# EMMC.net
KiCad netlist of a schematic drawn in Altium Designer
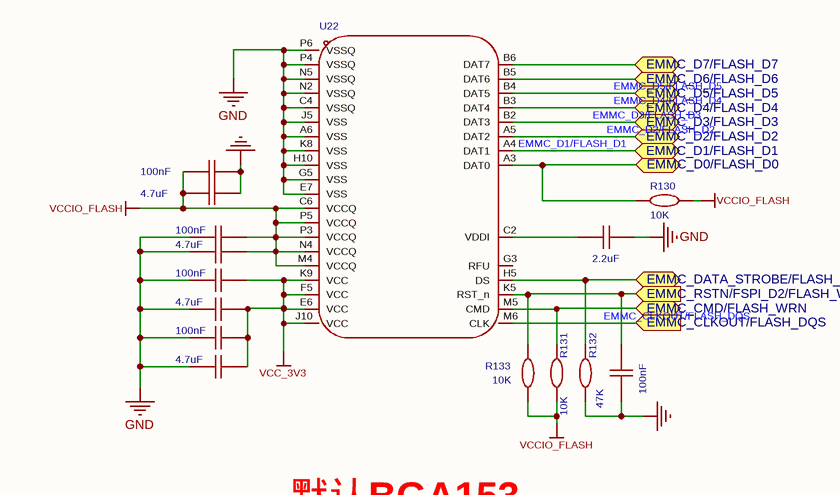
[diagram p0: EMMC.schdoc]

(export (version "E")
  (design (tool "Eeschema 10.0.6"))
  (components
    (comp (ref "C251")
      (value "100nF")
      (footprint "c0402-nsk")
      (description "容值:100nF;精度:±10%;额定电压:50V;材质(温度系数):X7R;")
      (fields (field (name "MANUFACTURER") "YAGEO(国巨)") (field (name "MANUFACTURERPART") "CC0603KRX7R9BB104"))
      (libsource (lib "altium-import") (part "root_0_CC0603KRX7R9BB104_"))
    )
    (comp (ref "C252")
      (value "4.7uF")
      (footprint "c0402-nsk")
      (description "容值:4.7uF;精度:±10%;额定电压:16V;材质(温度系数):X5R;")
      (fields (field (name "MANUFACTURER") "SAMSUNG(三星)") (field (name "MANUFACTURERPART") "CL10A475KO8NNNC"))
      (libsource (lib "altium-import") (part "root_0_CL10A475KO8NNNC_"))
    )
    (comp (ref "C253")
      (value "100nF")
      (footprint "c0402-nsk")
      (description "容值:100nF;精度:±10%;额定电压:50V;材质(温度系数):X7R;")
      (fields (field (name "MANUFACTURER") "YAGEO(国巨)") (field (name "MANUFACTURERPART") "CC0603KRX7R9BB104"))
      (libsource (lib "altium-import") (part "root_0_CC0603KRX7R9BB104_"))
    )
    (comp (ref "C254")
      (value "4.7uF")
      (footprint "c0402-nsk")
      (description "容值:4.7uF;精度:±10%;额定电压:16V;材质(温度系数):X5R;")
      (fields (field (name "MANUFACTURER") "SAMSUNG(三星)") (field (name "MANUFACTURERPART") "CL10A475KO8NNNC"))
      (libsource (lib "altium-import") (part "root_0_CL10A475KO8NNNC_"))
    )
    (comp (ref "C255")
      (value "2.2uF")
      (footprint "c0402-nsk")
      (description "容值:2.2uF;精度:±10%;额定电压:16V;材质(温度系数):X5R;")
      (fields (field (name "MANUFACTURER") "SAMSUNG(三星)") (field (name "MANUFACTURERPART") "CL10A225KO8NNNC"))
      (libsource (lib "altium-import") (part "root_2_CL10A225KO8NNNC_"))
    )
    (comp (ref "C256")
      (value "100nF")
      (footprint "c0402-nsk")
      (description "容值:100nF;精度:±10%;额定电压:50V;材质(温度系数):X7R;")
      (fields (field (name "MANUFACTURER") "YAGEO(国巨)") (field (name "MANUFACTURERPART") "CC0603KRX7R9BB104"))
      (libsource (lib "altium-import") (part "root_0_CC0603KRX7R9BB104_"))
    )
    (comp (ref "C257")
      (value "4.7uF")
      (footprint "c0402-nsk")
      (description "容值:4.7uF;精度:±10%;额定电压:16V;材质(温度系数):X5R;")
      (fields (field (name "MANUFACTURER") "SAMSUNG(三星)") (field (name "MANUFACTURERPART") "CL10A475KO8NNNC"))
      (libsource (lib "altium-import") (part "root_0_CL10A475KO8NNNC_"))
    )
    (comp (ref "C258")
      (value "100nF")
      (footprint "c0402-nsk")
      (description "容值:100nF;精度:±10%;额定电压:50V;材质(温度系数):X7R;")
      (fields (field (name "MANUFACTURER") "YAGEO(国巨)") (field (name "MANUFACTURERPART") "CC0603KRX7R9BB104"))
      (libsource (lib "altium-import") (part "root_0_CC0603KRX7R9BB104_"))
    )
    (comp (ref "C259")
      (value "4.7uF")
      (footprint "c0402-nsk")
      (description "容值:4.7uF;精度:±10%;额定电压:16V;材质(温度系数):X5R;")
      (fields (field (name "MANUFACTURER") "SAMSUNG(三星)") (field (name "MANUFACTURERPART") "CL10A475KO8NNNC"))
      (libsource (lib "altium-import") (part "root_0_CL10A475KO8NNNC_"))
    )
    (comp (ref "C260")
      (value "100nF")
      (footprint "c0402-nsk")
      (description "容值:4.7uF;精度:±10%;额定电压:16V;材质(温度系数):X5R;")
      (fields (field (name "MANUFACTURER") "SAMSUNG(三星)") (field (name "MANUFACTURERPART") "CL10A475KO8NNNC"))
      (libsource (lib "altium-import") (part "root_1_CL10A475KO8NNNC_"))
    )
    (comp (ref "R130")
      (value "10K")
      (footprint "R0402")
      (libsource (lib "altium-import") (part "root_0_Res_0402_"))
    )
    (comp (ref "R131")
      (value "10K")
      (footprint "R0402")
      (libsource (lib "altium-import") (part "root_1_Res_0402_"))
    )
    (comp (ref "R132")
      (value "47K")
      (footprint "R0402")
      (libsource (lib "altium-import") (part "root_1_Res_0402_"))
    )
    (comp (ref "R133")
      (value "10K")
      (footprint "R0402")
      (libsource (lib "altium-import") (part "root_1_Res_0402_"))
    )
    (comp (ref "U22")
      (value "~")
      (footprint "fbga-153_l13.0-w11.5-p0.50_klmag1jetd-b041")
      (fields
        (field (name "MANUFACTURER") "Kingston(金士顿)")
        (field (name "MANUFACTURERPART") "EMMC04G-M627-A01")
      )
      (libsource (lib "altium-import") (part "root_0_EMMC BGA153_"))
    )
  )
  (nets
    (net (code "1") (name "/EMMC_CLKOUT{slash}FLASH_DQS") (class "Default")
      (node (ref "U22") (pin "M6") (pinfunction "CLK_M6") (pintype "passive"))
    )
    (net (code "2") (name "/EMMC_CMD{slash}FLASH_WRN") (class "Default")
      (node (ref "R131") (pin "2") (pinfunction "2_2") (pintype "passive"))
      (node (ref "U22") (pin "M5") (pinfunction "CMD_M5") (pintype "passive"))
    )
    (net (code "3") (name "/EMMC_D0{slash}FLASH_D0") (class "Default")
      (node (ref "R130") (pin "1") (pinfunction "1_1") (pintype "passive"))
      (node (ref "U22") (pin "A3") (pinfunction "DAT0_A3") (pintype "passive"))
    )
    (net (code "4") (name "/EMMC_D1{slash}FLASH_D1") (class "Default")
      (node (ref "U22") (pin "A4") (pinfunction "DAT1_A4") (pintype "passive"))
    )
    (net (code "5") (name "/EMMC_D2{slash}FLASH_D2") (class "Default")
      (node (ref "U22") (pin "A5") (pinfunction "DAT2_A5") (pintype "passive"))
    )
    (net (code "6") (name "/EMMC_D3{slash}FLASH_D3") (class "Default")
      (node (ref "U22") (pin "B2") (pinfunction "DAT3_B2") (pintype "passive"))
    )
    (net (code "7") (name "/EMMC_D4{slash}FLASH_D4") (class "Default")
      (node (ref "U22") (pin "B3") (pinfunction "DAT4_B3") (pintype "passive"))
    )
    (net (code "8") (name "/EMMC_D5{slash}FLASH_D5") (class "Default")
      (node (ref "U22") (pin "B4") (pinfunction "DAT5_B4") (pintype "passive"))
    )
    (net (code "9") (name "/EMMC_D6{slash}FLASH_D6") (class "Default")
      (node (ref "U22") (pin "B5") (pinfunction "DAT6_B5") (pintype "passive"))
    )
    (net (code "10") (name "/EMMC_D7{slash}FLASH_D7") (class "Default")
      (node (ref "U22") (pin "B6") (pinfunction "DAT7_B6") (pintype "passive"))
    )
    (net (code "11") (name "/EMMC_DATA_STROBE{slash}FLASH_CLE") (class "Default")
      (node (ref "R132") (pin "2") (pinfunction "2_2") (pintype "passive"))
      (node (ref "U22") (pin "H5") (pinfunction "DS_H5") (pintype "passive"))
    )
    (net (code "12") (name "/EMMC_RSTN{slash}FSPI_D2{slash}FLASH_WPN") (class "Default")
      (node (ref "C260") (pin "2") (pinfunction "2_2") (pintype "passive"))
      (node (ref "R133") (pin "2") (pinfunction "2_2") (pintype "passive"))
      (node (ref "U22") (pin "K5") (pinfunction "RST_n_K5") (pintype "passive"))
    )
    (net (code "13") (name "GND") (class "Default")
      (node (ref "C251") (pin "2") (pinfunction "2_2") (pintype "passive"))
      (node (ref "C252") (pin "2") (pinfunction "2_2") (pintype "passive"))
      (node (ref "C253") (pin "1") (pinfunction "1_1") (pintype "passive"))
      (node (ref "C254") (pin "1") (pinfunction "1_1") (pintype "passive"))
      (node (ref "C255") (pin "1") (pinfunction "1_1") (pintype "passive"))
      (node (ref "C256") (pin "1") (pinfunction "1_1") (pintype "passive"))
      (node (ref "C257") (pin "1") (pinfunction "1_1") (pintype "passive"))
      (node (ref "C258") (pin "1") (pinfunction "1_1") (pintype "passive"))
      (node (ref "C259") (pin "1") (pinfunction "1_1") (pintype "passive"))
      (node (ref "C260") (pin "1") (pinfunction "1_1") (pintype "passive"))
      (node (ref "R132") (pin "1") (pinfunction "1_1") (pintype "passive"))
      (node (ref "U22") (pin "A6") (pinfunction "VSS_A6") (pintype "passive"))
      (node (ref "U22") (pin "C4") (pinfunction "VSSQ_C4") (pintype "passive"))
      (node (ref "U22") (pin "E7") (pinfunction "VSS_E7") (pintype "passive"))
      (node (ref "U22") (pin "G5") (pinfunction "VSS_G5") (pintype "passive"))
      (node (ref "U22") (pin "H10") (pinfunction "VSS_H10") (pintype "passive"))
      (node (ref "U22") (pin "J5") (pinfunction "VSS_J5") (pintype "passive"))
      (node (ref "U22") (pin "K8") (pinfunction "VSS_K8") (pintype "passive"))
      (node (ref "U22") (pin "N2") (pinfunction "VSSQ_N2") (pintype "passive"))
      (node (ref "U22") (pin "N5") (pinfunction "VSSQ_N5") (pintype "passive"))
      (node (ref "U22") (pin "P4") (pinfunction "VSSQ_P4") (pintype "passive"))
      (node (ref "U22") (pin "P6") (pinfunction "VSSQ_P6") (pintype "passive"))
    )
    (net (code "14") (name "Net-(U22-VDDI)") (class "Default")
      (node (ref "C255") (pin "2") (pinfunction "2_2") (pintype "passive"))
      (node (ref "U22") (pin "C2") (pinfunction "VDDI_C2") (pintype "passive"))
    )
    (net (code "15") (name "VCCIO_FLASH") (class "Default")
      (node (ref "C251") (pin "1") (pinfunction "1_1") (pintype "passive"))
      (node (ref "C252") (pin "1") (pinfunction "1_1") (pintype "passive"))
      (node (ref "C253") (pin "2") (pinfunction "2_2") (pintype "passive"))
      (node (ref "C254") (pin "2") (pinfunction "2_2") (pintype "passive"))
      (node (ref "R130") (pin "2") (pinfunction "2_2") (pintype "passive"))
      (node (ref "R131") (pin "1") (pinfunction "1_1") (pintype "passive"))
      (node (ref "R133") (pin "1") (pinfunction "1_1") (pintype "passive"))
      (node (ref "U22") (pin "C6") (pinfunction "VCCQ_C6") (pintype "passive"))
      (node (ref "U22") (pin "M4") (pinfunction "VCCQ_M4") (pintype "passive"))
      (node (ref "U22") (pin "N4") (pinfunction "VCCQ_N4") (pintype "passive"))
      (node (ref "U22") (pin "P3") (pinfunction "VCCQ_P3") (pintype "passive"))
      (node (ref "U22") (pin "P5") (pinfunction "VCCQ_P5") (pintype "passive"))
    )
    (net (code "16") (name "VCC_3V3") (class "Default")
      (node (ref "C256") (pin "2") (pinfunction "2_2") (pintype "passive"))
      (node (ref "C257") (pin "2") (pinfunction "2_2") (pintype "passive"))
      (node (ref "C258") (pin "2") (pinfunction "2_2") (pintype "passive"))
      (node (ref "C259") (pin "2") (pinfunction "2_2") (pintype "passive"))
      (node (ref "U22") (pin "E6") (pinfunction "VCC_E6") (pintype "passive"))
      (node (ref "U22") (pin "F5") (pinfunction "VCC_F5") (pintype "passive"))
      (node (ref "U22") (pin "J10") (pinfunction "VCC_J10") (pintype "passive"))
      (node (ref "U22") (pin "K9") (pinfunction "VCC_K9") (pintype "passive"))
    )
    (net (code "17") (name "unconnected-(U22-RFU-PadG3)") (class "Default")
      (node (ref "U22") (pin "G3") (pinfunction "RFU_G3") (pintype "passive"))
    )
  )
)
